# Morpheus_conector.net
KiCad netlist of a schematic drawn in Altium Designer
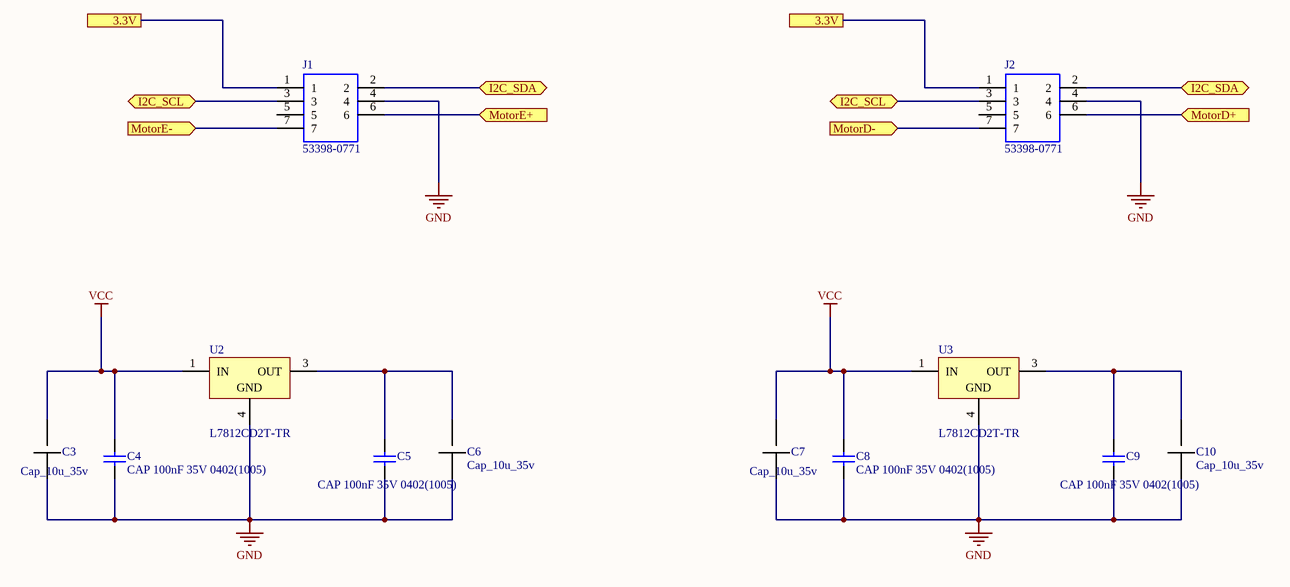
[diagram p0: Morpheus_conector.SchDoc]

(export (version "E")
  (design (tool "Eeschema 10.0.6"))
  (components
    (comp (ref "C3")
      (value "Cap_10u_35v")
      (footprint "Passives:CAP POL 2917/7343")
      (description "80-T491D106M35AT7280")
      (libsource (lib "LibSanhaço2017") (part "Cap_10u_35v"))
    )
    (comp (ref "C4")
      (value "CAP 100nF 35V 0402(1005)")
      (footprint "CAPC0402(1005)60_N")
      (fields (field (name "TOLERANCE") "Â±20%"))
      (libsource (lib "CAP 0402 100nF 35V") (part "CMP-1034-02076-1"))
    )
    (comp (ref "C5")
      (value "CAP 100nF 35V 0402(1005)")
      (footprint "CAPC0402(1005)60_N")
      (fields (field (name "TOLERANCE") "Â±20%"))
      (libsource (lib "CAP 0402 100nF 35V") (part "CMP-1034-02076-1"))
    )
    (comp (ref "C6")
      (value "Cap_10u_35v")
      (footprint "Passives:CAP POL 2917/7343")
      (description "80-T491D106M35AT7280")
      (libsource (lib "LibSanhaço2017") (part "Cap_10u_35v"))
    )
    (comp (ref "C7")
      (value "Cap_10u_35v")
      (footprint "Passives:CAP POL 2917/7343")
      (description "80-T491D106M35AT7280")
      (libsource (lib "LibSanhaço2017") (part "Cap_10u_35v"))
    )
    (comp (ref "C8")
      (value "CAP 100nF 35V 0402(1005)")
      (footprint "CAPC0402(1005)60_N")
      (fields (field (name "TOLERANCE") "Â±20%"))
      (libsource (lib "CAP 0402 100nF 35V") (part "CMP-1034-02076-1"))
    )
    (comp (ref "C9")
      (value "CAP 100nF 35V 0402(1005)")
      (footprint "CAPC0402(1005)60_N")
      (fields (field (name "TOLERANCE") "Â±20%"))
      (libsource (lib "CAP 0402 100nF 35V") (part "CMP-1034-02076-1"))
    )
    (comp (ref "C10")
      (value "Cap_10u_35v")
      (footprint "Passives:CAP POL 2917/7343")
      (description "80-T491D106M35AT7280")
      (libsource (lib "LibSanhaço2017") (part "Cap_10u_35v"))
    )
    (comp (ref "J1")
      (value "53398-0771")
      (footprint "53398-0771")
      (fields (field (name "RS PART NUMBER") "5427220P"))
      (libsource (lib "53398-0771") (part "53398-0771"))
    )
    (comp (ref "J2")
      (value "53398-0771")
      (footprint "53398-0771")
      (fields (field (name "RS PART NUMBER") "5427220P"))
      (libsource (lib "53398-0771") (part "53398-0771"))
    )
    (comp (ref "U2")
      (value "L7812CD2T-TR")
      (footprint "TO-263_N")
      (description "Positive Voltage Regulator, 3-Pin D2PAK, Tape and Reel")
      (libsource (lib "L7812CD2T-TR") (part "CMP-0244-00182-1"))
    )
    (comp (ref "U3")
      (value "L7812CD2T-TR")
      (footprint "TO-263_N")
      (description "Positive Voltage Regulator, 3-Pin D2PAK, Tape and Reel")
      (libsource (lib "L7812CD2T-TR") (part "CMP-0244-00182-1"))
    )
  )
  (nets
    (net (code "1") (name "/3.3V") (class "Default")
      (node (ref "J1") (pin "1") (pinfunction "1_1") (pintype "passive"))
      (node (ref "J2") (pin "1") (pinfunction "1_1") (pintype "passive"))
    )
    (net (code "2") (name "/I2C_SCL") (class "Default")
      (node (ref "J1") (pin "3") (pinfunction "3_3") (pintype "passive"))
      (node (ref "J2") (pin "3") (pinfunction "3_3") (pintype "passive"))
    )
    (net (code "3") (name "/I2C_SDA") (class "Default")
      (node (ref "J1") (pin "2") (pinfunction "2_2") (pintype "passive"))
      (node (ref "J2") (pin "2") (pinfunction "2_2") (pintype "passive"))
    )
    (net (code "4") (name "/MotorD+") (class "Default")
      (node (ref "J2") (pin "6") (pinfunction "6_6") (pintype "passive"))
    )
    (net (code "5") (name "/MotorD-") (class "Default")
      (node (ref "J2") (pin "7") (pinfunction "7_7") (pintype "passive"))
    )
    (net (code "6") (name "/MotorE+") (class "Default")
      (node (ref "J1") (pin "6") (pinfunction "6_6") (pintype "passive"))
    )
    (net (code "7") (name "/MotorE-") (class "Default")
      (node (ref "J1") (pin "7") (pinfunction "7_7") (pintype "passive"))
    )
    (net (code "8") (name "GND") (class "Default")
      (node (ref "C10") (pin "1") (pinfunction "1_1") (pintype "passive"))
      (node (ref "C3") (pin "1") (pinfunction "1_1") (pintype "passive"))
      (node (ref "C4") (pin "1") (pinfunction "1_1") (pintype "passive"))
      (node (ref "C5") (pin "1") (pinfunction "1_1") (pintype "passive"))
      (node (ref "C6") (pin "1") (pinfunction "1_1") (pintype "passive"))
      (node (ref "C7") (pin "1") (pinfunction "1_1") (pintype "passive"))
      (node (ref "C8") (pin "1") (pinfunction "1_1") (pintype "passive"))
      (node (ref "C9") (pin "1") (pinfunction "1_1") (pintype "passive"))
      (node (ref "J1") (pin "4") (pinfunction "4_4") (pintype "passive"))
      (node (ref "J2") (pin "4") (pinfunction "4_4") (pintype "passive"))
      (node (ref "U2") (pin "4") (pinfunction "GND_4") (pintype "power_in"))
      (node (ref "U3") (pin "4") (pinfunction "GND_4") (pintype "power_in"))
    )
    (net (code "9") (name "Net-(U2-OUT)") (class "Default")
      (node (ref "C5") (pin "2") (pinfunction "2_2") (pintype "passive"))
      (node (ref "C6") (pin "2") (pinfunction "2_2") (pintype "passive"))
      (node (ref "U2") (pin "3") (pinfunction "OUT_3") (pintype "power_in"))
    )
    (net (code "10") (name "Net-(U3-OUT)") (class "Default")
      (node (ref "C10") (pin "2") (pinfunction "2_2") (pintype "passive"))
      (node (ref "C9") (pin "2") (pinfunction "2_2") (pintype "passive"))
      (node (ref "U3") (pin "3") (pinfunction "OUT_3") (pintype "power_in"))
    )
    (net (code "11") (name "VCC") (class "Default")
      (node (ref "C3") (pin "2") (pinfunction "2_2") (pintype "passive"))
      (node (ref "C4") (pin "2") (pinfunction "2_2") (pintype "passive"))
      (node (ref "C7") (pin "2") (pinfunction "2_2") (pintype "passive"))
      (node (ref "C8") (pin "2") (pinfunction "2_2") (pintype "passive"))
      (node (ref "U2") (pin "1") (pinfunction "IN_1") (pintype "power_in"))
      (node (ref "U3") (pin "1") (pinfunction "IN_1") (pintype "power_in"))
    )
    (net (code "12") (name "unconnected-(J1-Pad5)") (class "Default")
      (node (ref "J1") (pin "5") (pinfunction "5_5") (pintype "passive"))
    )
    (net (code "13") (name "unconnected-(J2-Pad5)") (class "Default")
      (node (ref "J2") (pin "5") (pinfunction "5_5") (pintype "passive"))
    )
  )
)
